# Controllers.net
KiCad netlist of a schematic drawn in Altium Designer
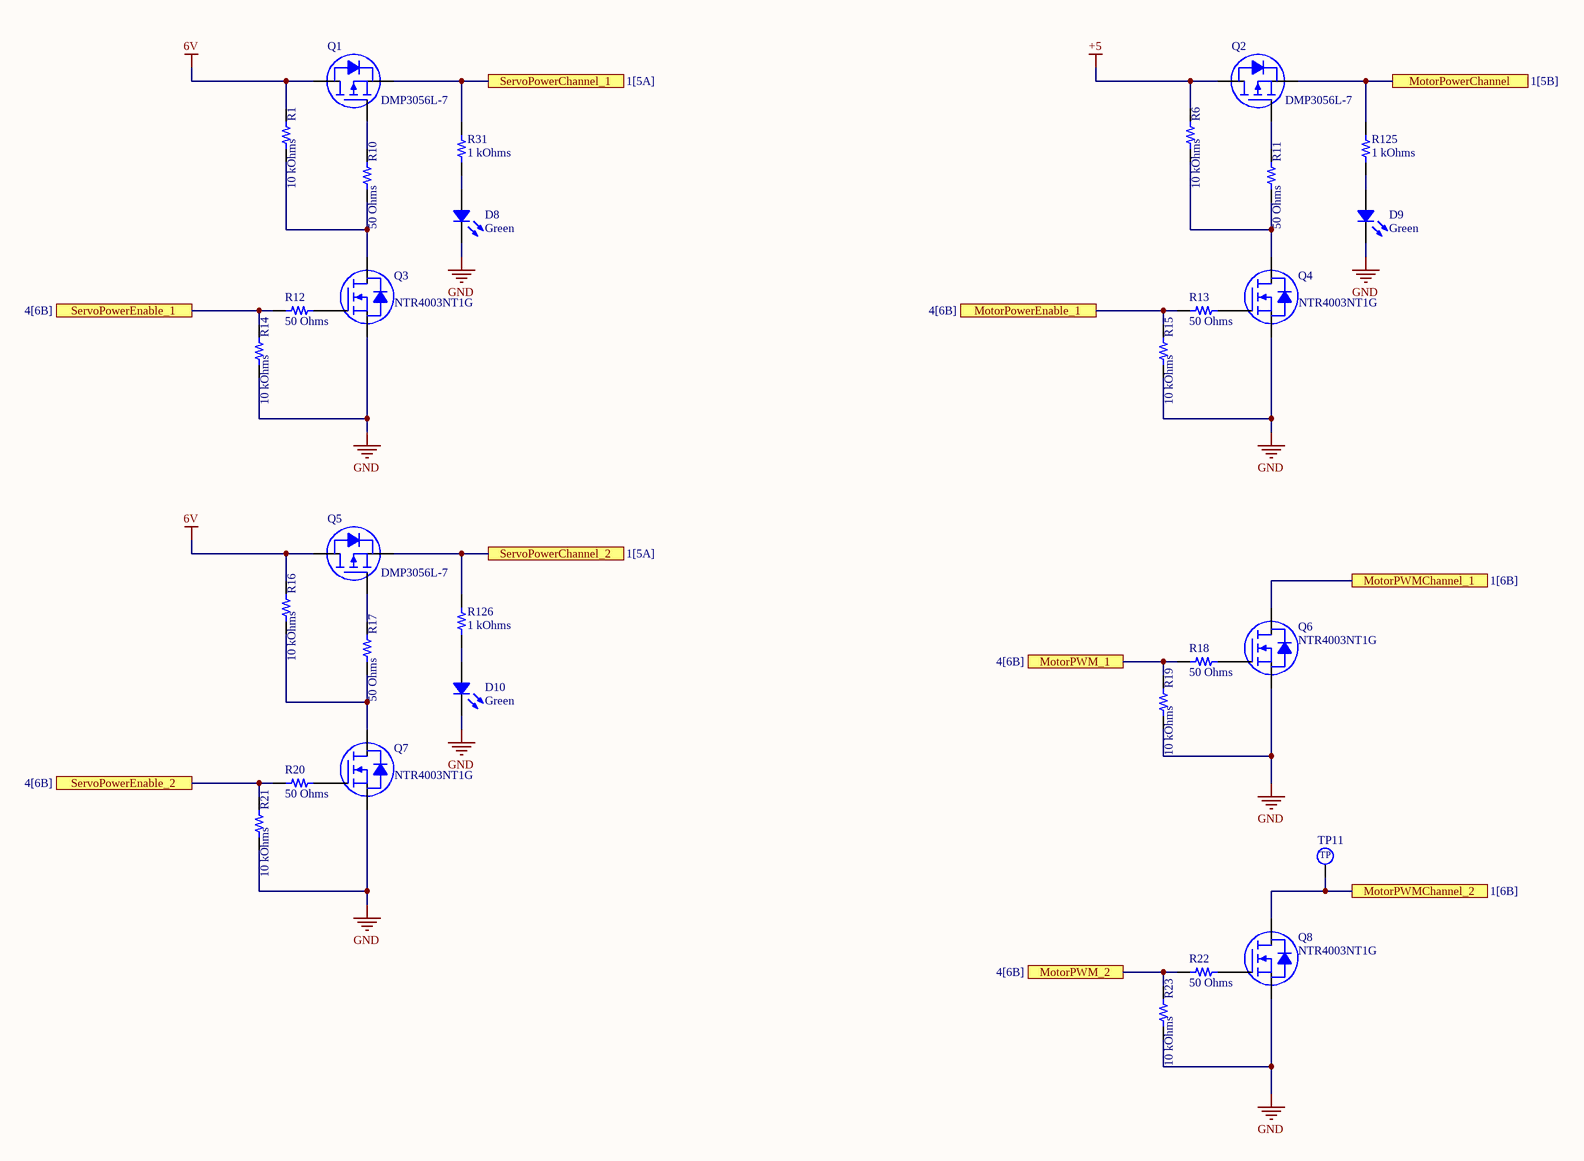
[diagram p0: Controllers.SchDoc]

(export (version "E")
  (design (tool "Eeschema 10.0.6"))
  (components
    (comp (ref "D8")
      (value "Green")
      (footprint "LED 0603_1608 GREEN")
      (description "LED GREEN CLEAR CHIP SMD")
      (fields (field (name "PART NUMBER") "LTST-C193KGKT-5A") (field (name "MANUFACTURER") "Lite-On Inc."))
      (libsource (lib "Celestial Altium Library - altium_library") (part "LED"))
    )
    (comp (ref "D9")
      (value "Green")
      (footprint "LED 0603_1608 GREEN")
      (description "LED GREEN CLEAR CHIP SMD")
      (fields (field (name "PART NUMBER") "LTST-C193KGKT-5A") (field (name "MANUFACTURER") "Lite-On Inc."))
      (libsource (lib "Celestial Altium Library - altium_library") (part "LED"))
    )
    (comp (ref "D10")
      (value "Green")
      (footprint "LED 0603_1608 GREEN")
      (description "LED GREEN CLEAR CHIP SMD")
      (fields (field (name "PART NUMBER") "LTST-C193KGKT-5A") (field (name "MANUFACTURER") "Lite-On Inc."))
      (libsource (lib "Celestial Altium Library - altium_library") (part "LED"))
    )
    (comp (ref "Q1")
      (value "DMP3056L-7")
      (footprint "DIODES SOT-23-3")
      (description "MOSFET P-CH 30V 4.3A SOT23")
      (fields (field (name "MANUFACTURER") "Diodes Incorporated"))
      (libsource (lib "Celestial Altium Library - altium_library") (part "DIODES MOSFET P-CH SOT-23-3"))
    )
    (comp (ref "Q2")
      (value "DMP3056L-7")
      (footprint "DIODES SOT-23-3")
      (description "MOSFET P-CH 30V 4.3A SOT23")
      (fields (field (name "MANUFACTURER") "Diodes Incorporated"))
      (libsource (lib "Celestial Altium Library - altium_library") (part "DIODES MOSFET P-CH SOT-23-3"))
    )
    (comp (ref "Q3")
      (value "NTR4003NT1G")
      (footprint "ON SEMI SOT-23-3")
      (description "MOSFET N-CH 30V 500MA SOT-23")
      (fields (field (name "MANUFACTURER") "ON Semiconductor"))
      (libsource (lib "Celestial Altium Library - altium_library") (part "ON SEMI MOSFET N-CH SOT-23-3"))
    )
    (comp (ref "Q4")
      (value "NTR4003NT1G")
      (footprint "ON SEMI SOT-23-3")
      (description "MOSFET N-CH 30V 500MA SOT-23")
      (fields (field (name "MANUFACTURER") "ON Semiconductor"))
      (libsource (lib "Celestial Altium Library - altium_library") (part "ON SEMI MOSFET N-CH SOT-23-3"))
    )
    (comp (ref "Q5")
      (value "DMP3056L-7")
      (footprint "DIODES SOT-23-3")
      (description "MOSFET P-CH 30V 4.3A SOT23")
      (fields (field (name "MANUFACTURER") "Diodes Incorporated"))
      (libsource (lib "Celestial Altium Library - altium_library") (part "DIODES MOSFET P-CH SOT-23-3"))
    )
    (comp (ref "Q6")
      (value "NTR4003NT1G")
      (footprint "ON SEMI SOT-23-3")
      (description "MOSFET N-CH 30V 500MA SOT-23")
      (fields (field (name "MANUFACTURER") "ON Semiconductor"))
      (libsource (lib "Celestial Altium Library - altium_library") (part "ON SEMI MOSFET N-CH SOT-23-3"))
    )
    (comp (ref "Q7")
      (value "NTR4003NT1G")
      (footprint "ON SEMI SOT-23-3")
      (description "MOSFET N-CH 30V 500MA SOT-23")
      (fields (field (name "MANUFACTURER") "ON Semiconductor"))
      (libsource (lib "Celestial Altium Library - altium_library") (part "ON SEMI MOSFET N-CH SOT-23-3"))
    )
    (comp (ref "Q8")
      (value "NTR4003NT1G")
      (footprint "ON SEMI SOT-23-3")
      (description "MOSFET N-CH 30V 500MA SOT-23")
      (fields (field (name "MANUFACTURER") "ON Semiconductor"))
      (libsource (lib "Celestial Altium Library - altium_library") (part "ON SEMI MOSFET N-CH SOT-23-3"))
    )
    (comp (ref "R1")
      (value "10 kOhms")
      (footprint "RES 0603_1608")
      (description "RES 10K OHM 5% 1/10W 0603")
      (fields
        (field (name "PART NUMBER") "RMCF0603JT10K0")
        (field (name "MANUFACTURER") "Stackpole Electronics Inc")
      )
      (libsource (lib "Celestial Altium Library - altium_library") (part "Resistor"))
    )
    (comp (ref "R6")
      (value "10 kOhms")
      (footprint "RES 0603_1608")
      (description "RES 10K OHM 5% 1/10W 0603")
      (fields
        (field (name "PART NUMBER") "RMCF0603JT10K0")
        (field (name "MANUFACTURER") "Stackpole Electronics Inc")
      )
      (libsource (lib "Celestial Altium Library - altium_library") (part "Resistor"))
    )
    (comp (ref "R10")
      (value "50 Ohms")
      (footprint "RES 0603_1608")
      (description "RES SMD 50 OHM 1% 1/10W 0603")
      (fields (field (name "PART NUMBER") "CRCW060350R0FKEA") (field (name "MANUFACTURER") "Vishay Dale"))
      (libsource (lib "Celestial Altium Library - altium_library") (part "Resistor"))
    )
    (comp (ref "R11")
      (value "50 Ohms")
      (footprint "RES 0603_1608")
      (description "RES SMD 50 OHM 1% 1/10W 0603")
      (fields (field (name "PART NUMBER") "CRCW060350R0FKEA") (field (name "MANUFACTURER") "Vishay Dale"))
      (libsource (lib "Celestial Altium Library - altium_library") (part "Resistor"))
    )
    (comp (ref "R12")
      (value "50 Ohms")
      (footprint "RES 0603_1608")
      (description "RES SMD 50 OHM 1% 1/10W 0603")
      (fields (field (name "PART NUMBER") "CRCW060350R0FKEA") (field (name "MANUFACTURER") "Vishay Dale"))
      (libsource (lib "Celestial Altium Library - altium_library") (part "Resistor"))
    )
    (comp (ref "R13")
      (value "50 Ohms")
      (footprint "RES 0603_1608")
      (description "RES SMD 50 OHM 1% 1/10W 0603")
      (fields (field (name "PART NUMBER") "CRCW060350R0FKEA") (field (name "MANUFACTURER") "Vishay Dale"))
      (libsource (lib "Celestial Altium Library - altium_library") (part "Resistor"))
    )
    (comp (ref "R14")
      (value "10 kOhms")
      (footprint "RES 0603_1608")
      (description "RES 10K OHM 5% 1/10W 0603")
      (fields
        (field (name "PART NUMBER") "RMCF0603JT10K0")
        (field (name "MANUFACTURER") "Stackpole Electronics Inc")
      )
      (libsource (lib "Celestial Altium Library - altium_library") (part "Resistor"))
    )
    (comp (ref "R15")
      (value "10 kOhms")
      (footprint "RES 0603_1608")
      (description "RES 10K OHM 5% 1/10W 0603")
      (fields
        (field (name "PART NUMBER") "RMCF0603JT10K0")
        (field (name "MANUFACTURER") "Stackpole Electronics Inc")
      )
      (libsource (lib "Celestial Altium Library - altium_library") (part "Resistor"))
    )
    (comp (ref "R16")
      (value "10 kOhms")
      (footprint "RES 0603_1608")
      (description "RES 10K OHM 5% 1/10W 0603")
      (fields
        (field (name "PART NUMBER") "RMCF0603JT10K0")
        (field (name "MANUFACTURER") "Stackpole Electronics Inc")
      )
      (libsource (lib "Celestial Altium Library - altium_library") (part "Resistor"))
    )
    (comp (ref "R17")
      (value "50 Ohms")
      (footprint "RES 0603_1608")
      (description "RES SMD 50 OHM 1% 1/10W 0603")
      (fields (field (name "PART NUMBER") "CRCW060350R0FKEA") (field (name "MANUFACTURER") "Vishay Dale"))
      (libsource (lib "Celestial Altium Library - altium_library") (part "Resistor"))
    )
    (comp (ref "R18")
      (value "50 Ohms")
      (footprint "RES 0603_1608")
      (description "RES SMD 50 OHM 1% 1/10W 0603")
      (fields (field (name "PART NUMBER") "CRCW060350R0FKEA") (field (name "MANUFACTURER") "Vishay Dale"))
      (libsource (lib "Celestial Altium Library - altium_library") (part "Resistor"))
    )
    (comp (ref "R19")
      (value "10 kOhms")
      (footprint "RES 0603_1608")
      (description "RES 10K OHM 5% 1/10W 0603")
      (fields
        (field (name "PART NUMBER") "RMCF0603JT10K0")
        (field (name "MANUFACTURER") "Stackpole Electronics Inc")
      )
      (libsource (lib "Celestial Altium Library - altium_library") (part "Resistor"))
    )
    (comp (ref "R20")
      (value "50 Ohms")
      (footprint "RES 0603_1608")
      (description "RES SMD 50 OHM 1% 1/10W 0603")
      (fields (field (name "PART NUMBER") "CRCW060350R0FKEA") (field (name "MANUFACTURER") "Vishay Dale"))
      (libsource (lib "Celestial Altium Library - altium_library") (part "Resistor"))
    )
    (comp (ref "R21")
      (value "10 kOhms")
      (footprint "RES 0603_1608")
      (description "RES 10K OHM 5% 1/10W 0603")
      (fields
        (field (name "PART NUMBER") "RMCF0603JT10K0")
        (field (name "MANUFACTURER") "Stackpole Electronics Inc")
      )
      (libsource (lib "Celestial Altium Library - altium_library") (part "Resistor"))
    )
    (comp (ref "R22")
      (value "50 Ohms")
      (footprint "RES 0603_1608")
      (description "RES SMD 50 OHM 1% 1/10W 0603")
      (fields (field (name "PART NUMBER") "CRCW060350R0FKEA") (field (name "MANUFACTURER") "Vishay Dale"))
      (libsource (lib "Celestial Altium Library - altium_library") (part "Resistor"))
    )
    (comp (ref "R23")
      (value "10 kOhms")
      (footprint "RES 0603_1608")
      (description "RES 10K OHM 5% 1/10W 0603")
      (fields
        (field (name "PART NUMBER") "RMCF0603JT10K0")
        (field (name "MANUFACTURER") "Stackpole Electronics Inc")
      )
      (libsource (lib "Celestial Altium Library - altium_library") (part "Resistor"))
    )
    (comp (ref "R31")
      (value "1 kOhms")
      (footprint "RES 0603_1608")
      (description "RES 1K OHM 1% 1/8W 0603")
      (fields
        (field (name "PART NUMBER") "RNCP0603FTD1K00")
        (field (name "MANUFACTURER") "Stackpole Electronics Inc")
      )
      (libsource (lib "Celestial Altium Library - altium_library") (part "Resistor"))
    )
    (comp (ref "R125")
      (value "1 kOhms")
      (footprint "RES 0603_1608")
      (description "RES 1K OHM 1% 1/8W 0603")
      (fields
        (field (name "PART NUMBER") "RNCP0603FTD1K00")
        (field (name "MANUFACTURER") "Stackpole Electronics Inc")
      )
      (libsource (lib "Celestial Altium Library - altium_library") (part "Resistor"))
    )
    (comp (ref "R126")
      (value "1 kOhms")
      (footprint "RES 0603_1608")
      (description "RES 1K OHM 1% 1/8W 0603")
      (fields
        (field (name "PART NUMBER") "RNCP0603FTD1K00")
        (field (name "MANUFACTURER") "Stackpole Electronics Inc")
      )
      (libsource (lib "Celestial Altium Library - altium_library") (part "Resistor"))
    )
    (comp (ref "TP11")
      (value "2.5mm_SMD_TestPoint")
      (footprint "2.5mm TestPoint")
      (libsource (lib "HAB_Assorted") (part "2.5mm_SMD_TestPoint"))
    )
  )
  (nets
    (net (code "1") (name "+5") (class "Default")
      (node (ref "Q2") (pin "3") (pinfunction "D_3") (pintype "passive"))
      (node (ref "R6") (pin "2") (pinfunction "2_2") (pintype "passive"))
    )
    (net (code "2") (name "/MotorPWMChannel_1") (class "Default")
      (node (ref "Q6") (pin "3") (pinfunction "D_3") (pintype "passive"))
    )
    (net (code "3") (name "/MotorPWMChannel_2") (class "Default")
      (node (ref "Q8") (pin "3") (pinfunction "D_3") (pintype "passive"))
      (node (ref "TP11") (pin "1") (pintype "passive"))
    )
    (net (code "4") (name "/MotorPWM_1") (class "Default")
      (node (ref "R18") (pin "2") (pinfunction "2_2") (pintype "passive"))
      (node (ref "R19") (pin "2") (pinfunction "2_2") (pintype "passive"))
    )
    (net (code "5") (name "/MotorPWM_2") (class "Default")
      (node (ref "R22") (pin "2") (pinfunction "2_2") (pintype "passive"))
      (node (ref "R23") (pin "2") (pinfunction "2_2") (pintype "passive"))
    )
    (net (code "6") (name "/MotorPowerChannel") (class "Default")
      (node (ref "Q2") (pin "2") (pinfunction "S_2") (pintype "passive"))
      (node (ref "R125") (pin "2") (pinfunction "2_2") (pintype "passive"))
    )
    (net (code "7") (name "/MotorPowerEnable_1") (class "Default")
      (node (ref "R13") (pin "2") (pinfunction "2_2") (pintype "passive"))
      (node (ref "R15") (pin "2") (pinfunction "2_2") (pintype "passive"))
    )
    (net (code "8") (name "/ServoPowerChannel_1") (class "Default")
      (node (ref "Q1") (pin "2") (pinfunction "S_2") (pintype "passive"))
      (node (ref "R31") (pin "2") (pinfunction "2_2") (pintype "passive"))
    )
    (net (code "9") (name "/ServoPowerChannel_2") (class "Default")
      (node (ref "Q5") (pin "2") (pinfunction "S_2") (pintype "passive"))
      (node (ref "R126") (pin "2") (pinfunction "2_2") (pintype "passive"))
    )
    (net (code "10") (name "/ServoPowerEnable_1") (class "Default")
      (node (ref "R12") (pin "2") (pinfunction "2_2") (pintype "passive"))
      (node (ref "R14") (pin "2") (pinfunction "2_2") (pintype "passive"))
    )
    (net (code "11") (name "/ServoPowerEnable_2") (class "Default")
      (node (ref "R20") (pin "2") (pinfunction "2_2") (pintype "passive"))
      (node (ref "R21") (pin "2") (pinfunction "2_2") (pintype "passive"))
    )
    (net (code "12") (name "6V") (class "Default")
      (node (ref "Q1") (pin "3") (pinfunction "D_3") (pintype "passive"))
      (node (ref "Q5") (pin "3") (pinfunction "D_3") (pintype "passive"))
      (node (ref "R1") (pin "2") (pinfunction "2_2") (pintype "passive"))
      (node (ref "R16") (pin "2") (pinfunction "2_2") (pintype "passive"))
    )
    (net (code "13") (name "GND") (class "Default")
      (node (ref "D10") (pin "2") (pinfunction "2_2") (pintype "passive"))
      (node (ref "D8") (pin "2") (pinfunction "2_2") (pintype "passive"))
      (node (ref "D9") (pin "2") (pinfunction "2_2") (pintype "passive"))
      (node (ref "Q3") (pin "2") (pinfunction "S_2") (pintype "passive"))
      (node (ref "Q4") (pin "2") (pinfunction "S_2") (pintype "passive"))
      (node (ref "Q6") (pin "2") (pinfunction "S_2") (pintype "passive"))
      (node (ref "Q7") (pin "2") (pinfunction "S_2") (pintype "passive"))
      (node (ref "Q8") (pin "2") (pinfunction "S_2") (pintype "passive"))
      (node (ref "R14") (pin "1") (pinfunction "1_1") (pintype "passive"))
      (node (ref "R15") (pin "1") (pinfunction "1_1") (pintype "passive"))
      (node (ref "R19") (pin "1") (pinfunction "1_1") (pintype "passive"))
      (node (ref "R21") (pin "1") (pinfunction "1_1") (pintype "passive"))
      (node (ref "R23") (pin "1") (pinfunction "1_1") (pintype "passive"))
    )
    (net (code "14") (name "Net-(D8-Pad1)") (class "Default")
      (node (ref "D8") (pin "1") (pinfunction "1_1") (pintype "passive"))
      (node (ref "R31") (pin "1") (pinfunction "1_1") (pintype "passive"))
    )
    (net (code "15") (name "Net-(D9-Pad1)") (class "Default")
      (node (ref "D9") (pin "1") (pinfunction "1_1") (pintype "passive"))
      (node (ref "R125") (pin "1") (pinfunction "1_1") (pintype "passive"))
    )
    (net (code "16") (name "Net-(D10-Pad1)") (class "Default")
      (node (ref "D10") (pin "1") (pinfunction "1_1") (pintype "passive"))
      (node (ref "R126") (pin "1") (pinfunction "1_1") (pintype "passive"))
    )
    (net (code "17") (name "Net-(Q1-G)") (class "Default")
      (node (ref "Q1") (pin "1") (pinfunction "G_1") (pintype "passive"))
      (node (ref "R10") (pin "2") (pinfunction "2_2") (pintype "passive"))
    )
    (net (code "18") (name "Net-(Q2-G)") (class "Default")
      (node (ref "Q2") (pin "1") (pinfunction "G_1") (pintype "passive"))
      (node (ref "R11") (pin "2") (pinfunction "2_2") (pintype "passive"))
    )
    (net (code "19") (name "Net-(Q3-D)") (class "Default")
      (node (ref "Q3") (pin "3") (pinfunction "D_3") (pintype "passive"))
      (node (ref "R1") (pin "1") (pinfunction "1_1") (pintype "passive"))
      (node (ref "R10") (pin "1") (pinfunction "1_1") (pintype "passive"))
    )
    (net (code "20") (name "Net-(Q3-G)") (class "Default")
      (node (ref "Q3") (pin "1") (pinfunction "G_1") (pintype "passive"))
      (node (ref "R12") (pin "1") (pinfunction "1_1") (pintype "passive"))
    )
    (net (code "21") (name "Net-(Q4-D)") (class "Default")
      (node (ref "Q4") (pin "3") (pinfunction "D_3") (pintype "passive"))
      (node (ref "R11") (pin "1") (pinfunction "1_1") (pintype "passive"))
      (node (ref "R6") (pin "1") (pinfunction "1_1") (pintype "passive"))
    )
    (net (code "22") (name "Net-(Q4-G)") (class "Default")
      (node (ref "Q4") (pin "1") (pinfunction "G_1") (pintype "passive"))
      (node (ref "R13") (pin "1") (pinfunction "1_1") (pintype "passive"))
    )
    (net (code "23") (name "Net-(Q5-G)") (class "Default")
      (node (ref "Q5") (pin "1") (pinfunction "G_1") (pintype "passive"))
      (node (ref "R17") (pin "2") (pinfunction "2_2") (pintype "passive"))
    )
    (net (code "24") (name "Net-(Q6-G)") (class "Default")
      (node (ref "Q6") (pin "1") (pinfunction "G_1") (pintype "passive"))
      (node (ref "R18") (pin "1") (pinfunction "1_1") (pintype "passive"))
    )
    (net (code "25") (name "Net-(Q7-D)") (class "Default")
      (node (ref "Q7") (pin "3") (pinfunction "D_3") (pintype "passive"))
      (node (ref "R16") (pin "1") (pinfunction "1_1") (pintype "passive"))
      (node (ref "R17") (pin "1") (pinfunction "1_1") (pintype "passive"))
    )
    (net (code "26") (name "Net-(Q7-G)") (class "Default")
      (node (ref "Q7") (pin "1") (pinfunction "G_1") (pintype "passive"))
      (node (ref "R20") (pin "1") (pinfunction "1_1") (pintype "passive"))
    )
    (net (code "27") (name "Net-(Q8-G)") (class "Default")
      (node (ref "Q8") (pin "1") (pinfunction "G_1") (pintype "passive"))
      (node (ref "R22") (pin "1") (pinfunction "1_1") (pintype "passive"))
    )
  )
)
